# Teensy-Maxuino-Slave-A4988-stepper_2x_sh.net
KiCad netlist of a schematic drawn in EAGLE
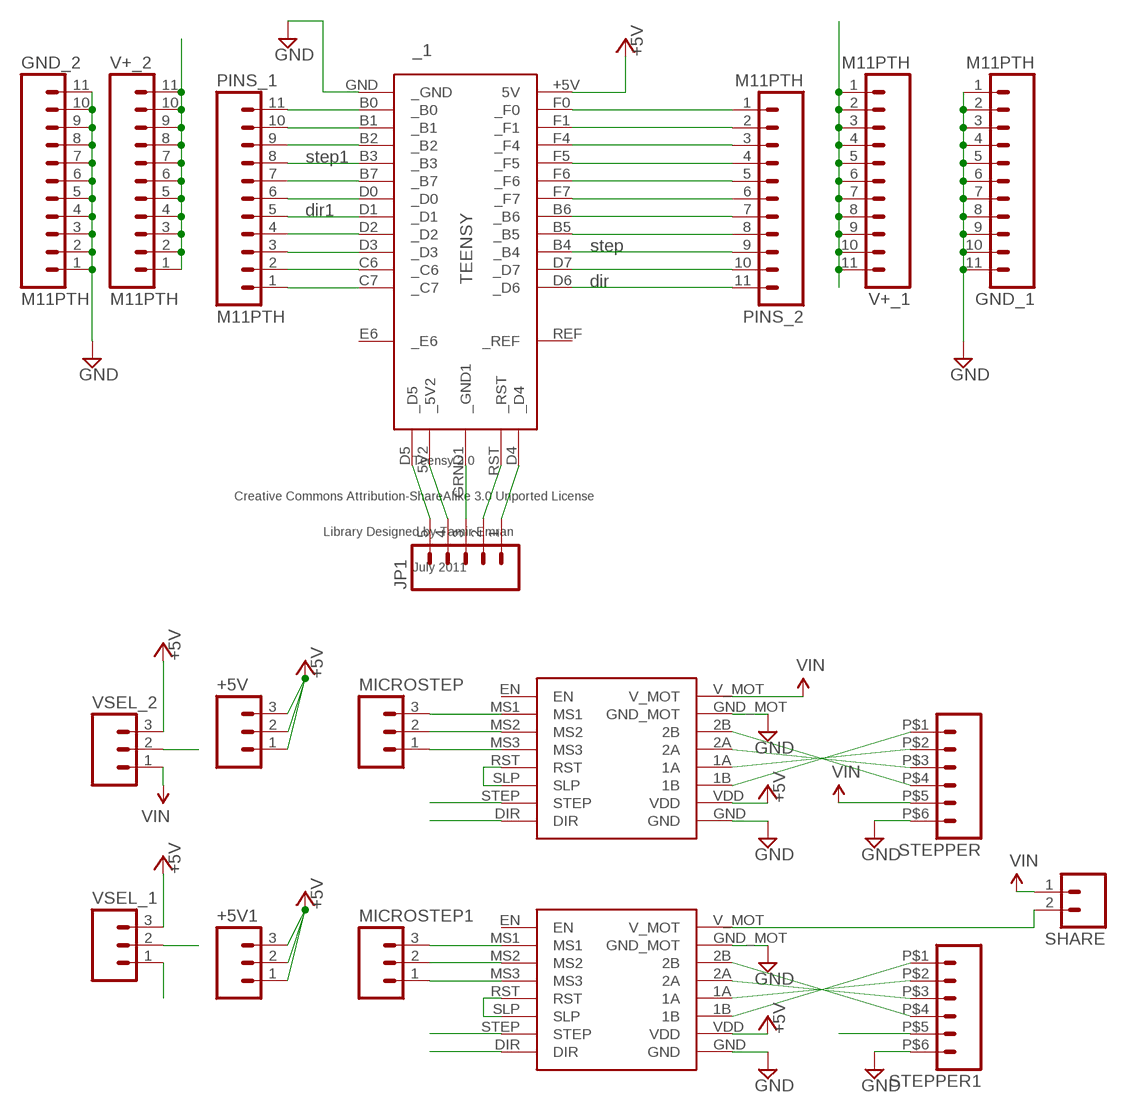
[diagram p0: schematic, sheet 1]

(export (version "E")
  (design (tool "Eeschema 10.0.6"))
  (components
    (comp (ref "+5V")
      (value "M03PTH")
      (footprint "eagle-import:1X03")
      (libsource (lib "eagle-import") (part "M03PTH"))
    )
    (comp (ref "+5V1")
      (value "M03PTH")
      (footprint "eagle-import:1X03")
      (libsource (lib "eagle-import") (part "M03PTH"))
    )
    (comp (ref "A4988_1")
      (value "POLOLU_A4988")
      (footprint "eagle-import:POLOLU_A4988")
      (libsource (lib "eagle-import") (part "POLOLU_A4988"))
    )
    (comp (ref "A4988_2")
      (value "POLOLU_A4988")
      (footprint "eagle-import:POLOLU_A4988")
      (libsource (lib "eagle-import") (part "POLOLU_A4988"))
    )
    (comp (ref "GND_1")
      (value "M11PTH")
      (footprint "eagle-import:1X11")
      (libsource (lib "eagle-import") (part "M11PTH"))
    )
    (comp (ref "GND_2")
      (value "M11PTH")
      (footprint "eagle-import:1X11")
      (libsource (lib "eagle-import") (part "M11PTH"))
    )
    (comp (ref "JP1")
      (value "M05PTH")
      (footprint "eagle-import:1X05")
      (libsource (lib "eagle-import") (part "M05PTH"))
    )
    (comp (ref "MICROSTEP")
      (value "M03PTH")
      (footprint "eagle-import:1X03")
      (libsource (lib "eagle-import") (part "M03PTH"))
    )
    (comp (ref "MICROSTEP1")
      (value "M03PTH")
      (footprint "eagle-import:1X03")
      (libsource (lib "eagle-import") (part "M03PTH"))
    )
    (comp (ref "PINS_1")
      (value "M11PTH")
      (footprint "eagle-import:1X11")
      (libsource (lib "eagle-import") (part "M11PTH"))
    )
    (comp (ref "PINS_2")
      (value "M11PTH")
      (footprint "eagle-import:1X11")
      (libsource (lib "eagle-import") (part "M11PTH"))
    )
    (comp (ref "SHARE")
      (value "M02PTH")
      (footprint "eagle-import:1X02")
      (libsource (lib "eagle-import") (part "M02PTH"))
    )
    (comp (ref "STEPPER")
      (value "M06")
      (footprint "eagle-import:SPRINGTERMINAL-2.54MM-6")
      (libsource (lib "eagle-import") (part "M06"))
    )
    (comp (ref "STEPPER1")
      (value "M06")
      (footprint "eagle-import:SPRINGTERMINAL-2.54MM-6")
      (libsource (lib "eagle-import") (part "M06"))
    )
    (comp (ref "V+_1")
      (value "M11PTH")
      (footprint "eagle-import:1X11")
      (libsource (lib "eagle-import") (part "M11PTH"))
    )
    (comp (ref "V+_2")
      (value "M11PTH")
      (footprint "eagle-import:1X11")
      (libsource (lib "eagle-import") (part "M11PTH"))
    )
    (comp (ref "VSEL_1")
      (value "M03PTH")
      (footprint "eagle-import:1X03")
      (libsource (lib "eagle-import") (part "M03PTH"))
    )
    (comp (ref "VSEL_2")
      (value "M03PTH")
      (footprint "eagle-import:1X03")
      (libsource (lib "eagle-import") (part "M03PTH"))
    )
    (comp (ref "_1")
      (value "TEENSY")
      (footprint "eagle-import:TEENSY")
      (libsource (lib "eagle-import") (part "TEENSY"))
    )
  )
  (nets
    (net (code "1") (name "+5V") (class "Default")
      (node (ref "+5V") (pin "1") (pinfunction "1_1") (pintype "passive"))
      (node (ref "+5V") (pin "2") (pinfunction "2_2") (pintype "passive"))
      (node (ref "+5V") (pin "3") (pinfunction "3_3") (pintype "passive"))
      (node (ref "+5V1") (pin "1") (pinfunction "1_1") (pintype "passive"))
      (node (ref "+5V1") (pin "2") (pinfunction "2_2") (pintype "passive"))
      (node (ref "+5V1") (pin "3") (pinfunction "3_3") (pintype "passive"))
      (node (ref "A4988_1") (pin "VDD") (pinfunction "VDD_VDD") (pintype "bidirectional"))
      (node (ref "A4988_2") (pin "VDD") (pinfunction "VDD_VDD") (pintype "bidirectional"))
      (node (ref "JP1") (pin "4") (pinfunction "4_4") (pintype "passive"))
      (node (ref "VSEL_1") (pin "3") (pinfunction "3_3") (pintype "passive"))
      (node (ref "VSEL_2") (pin "3") (pinfunction "3_3") (pintype "passive"))
      (node (ref "_1") (pin "+5V") (pinfunction "5V_+5V") (pintype "bidirectional"))
      (node (ref "_1") (pin "5V2") (pinfunction "_5V2_5V2") (pintype "bidirectional"))
    )
    (net (code "2") (name "/DIR") (class "Default")
      (node (ref "A4988_1") (pin "DIR") (pinfunction "DIR_DIR") (pintype "bidirectional"))
      (node (ref "PINS_2") (pin "11") (pinfunction "11_11") (pintype "passive"))
      (node (ref "_1") (pin "D6") (pinfunction "_D6_D6") (pintype "bidirectional"))
    )
    (net (code "3") (name "/DIR1") (class "Default")
      (node (ref "A4988_2") (pin "DIR") (pinfunction "DIR_DIR") (pintype "bidirectional"))
      (node (ref "PINS_1") (pin "5") (pinfunction "5_5") (pintype "passive"))
      (node (ref "_1") (pin "D1") (pinfunction "_D1_D1") (pintype "bidirectional"))
    )
    (net (code "4") (name "/STEP") (class "Default")
      (node (ref "A4988_1") (pin "STEP") (pinfunction "STEP_STEP") (pintype "bidirectional"))
      (node (ref "PINS_2") (pin "9") (pinfunction "9_9") (pintype "passive"))
      (node (ref "_1") (pin "B4") (pinfunction "_B4_B4") (pintype "bidirectional"))
    )
    (net (code "5") (name "/STEP1") (class "Default")
      (node (ref "A4988_2") (pin "STEP") (pinfunction "STEP_STEP") (pintype "bidirectional"))
      (node (ref "PINS_1") (pin "8") (pinfunction "8_8") (pintype "passive"))
      (node (ref "_1") (pin "B3") (pinfunction "_B3_B3") (pintype "bidirectional"))
    )
    (net (code "6") (name "/V+_1") (class "Default")
      (node (ref "V+_1") (pin "1") (pinfunction "1_1") (pintype "passive"))
      (node (ref "V+_1") (pin "10") (pinfunction "10_10") (pintype "passive"))
      (node (ref "V+_1") (pin "11") (pinfunction "11_11") (pintype "passive"))
      (node (ref "V+_1") (pin "2") (pinfunction "2_2") (pintype "passive"))
      (node (ref "V+_1") (pin "3") (pinfunction "3_3") (pintype "passive"))
      (node (ref "V+_1") (pin "4") (pinfunction "4_4") (pintype "passive"))
      (node (ref "V+_1") (pin "5") (pinfunction "5_5") (pintype "passive"))
      (node (ref "V+_1") (pin "6") (pinfunction "6_6") (pintype "passive"))
      (node (ref "V+_1") (pin "7") (pinfunction "7_7") (pintype "passive"))
      (node (ref "V+_1") (pin "8") (pinfunction "8_8") (pintype "passive"))
      (node (ref "V+_1") (pin "9") (pinfunction "9_9") (pintype "passive"))
      (node (ref "VSEL_1") (pin "2") (pinfunction "2_2") (pintype "passive"))
    )
    (net (code "7") (name "/V+_2") (class "Default")
      (node (ref "V+_2") (pin "1") (pinfunction "1_1") (pintype "passive"))
      (node (ref "V+_2") (pin "10") (pinfunction "10_10") (pintype "passive"))
      (node (ref "V+_2") (pin "11") (pinfunction "11_11") (pintype "passive"))
      (node (ref "V+_2") (pin "2") (pinfunction "2_2") (pintype "passive"))
      (node (ref "V+_2") (pin "3") (pinfunction "3_3") (pintype "passive"))
      (node (ref "V+_2") (pin "4") (pinfunction "4_4") (pintype "passive"))
      (node (ref "V+_2") (pin "5") (pinfunction "5_5") (pintype "passive"))
      (node (ref "V+_2") (pin "6") (pinfunction "6_6") (pintype "passive"))
      (node (ref "V+_2") (pin "7") (pinfunction "7_7") (pintype "passive"))
      (node (ref "V+_2") (pin "8") (pinfunction "8_8") (pintype "passive"))
      (node (ref "V+_2") (pin "9") (pinfunction "9_9") (pintype "passive"))
      (node (ref "VSEL_2") (pin "2") (pinfunction "2_2") (pintype "passive"))
    )
    (net (code "8") (name "/VIN_2") (class "Default")
      (node (ref "A4988_2") (pin "V_MOT") (pinfunction "V_MOT_V_MOT") (pintype "bidirectional"))
      (node (ref "SHARE") (pin "2") (pinfunction "2_2") (pintype "passive"))
      (node (ref "STEPPER1") (pin "P$5") (pinfunction "5_P$5") (pintype "passive"))
      (node (ref "VSEL_1") (pin "1") (pinfunction "1_1") (pintype "passive"))
    )
    (net (code "9") (name "GND") (class "Default")
      (node (ref "A4988_1") (pin "GND") (pinfunction "GND_GND") (pintype "bidirectional"))
      (node (ref "A4988_1") (pin "GND_MOT") (pinfunction "GND_MOT_GND_MOT") (pintype "bidirectional"))
      (node (ref "A4988_2") (pin "GND") (pinfunction "GND_GND") (pintype "bidirectional"))
      (node (ref "A4988_2") (pin "GND_MOT") (pinfunction "GND_MOT_GND_MOT") (pintype "bidirectional"))
      (node (ref "GND_1") (pin "1") (pinfunction "1_1") (pintype "passive"))
      (node (ref "GND_1") (pin "10") (pinfunction "10_10") (pintype "passive"))
      (node (ref "GND_1") (pin "11") (pinfunction "11_11") (pintype "passive"))
      (node (ref "GND_1") (pin "2") (pinfunction "2_2") (pintype "passive"))
      (node (ref "GND_1") (pin "3") (pinfunction "3_3") (pintype "passive"))
      (node (ref "GND_1") (pin "4") (pinfunction "4_4") (pintype "passive"))
      (node (ref "GND_1") (pin "5") (pinfunction "5_5") (pintype "passive"))
      (node (ref "GND_1") (pin "6") (pinfunction "6_6") (pintype "passive"))
      (node (ref "GND_1") (pin "7") (pinfunction "7_7") (pintype "passive"))
      (node (ref "GND_1") (pin "8") (pinfunction "8_8") (pintype "passive"))
      (node (ref "GND_1") (pin "9") (pinfunction "9_9") (pintype "passive"))
      (node (ref "GND_2") (pin "1") (pinfunction "1_1") (pintype "passive"))
      (node (ref "GND_2") (pin "10") (pinfunction "10_10") (pintype "passive"))
      (node (ref "GND_2") (pin "11") (pinfunction "11_11") (pintype "passive"))
      (node (ref "GND_2") (pin "2") (pinfunction "2_2") (pintype "passive"))
      (node (ref "GND_2") (pin "3") (pinfunction "3_3") (pintype "passive"))
      (node (ref "GND_2") (pin "4") (pinfunction "4_4") (pintype "passive"))
      (node (ref "GND_2") (pin "5") (pinfunction "5_5") (pintype "passive"))
      (node (ref "GND_2") (pin "6") (pinfunction "6_6") (pintype "passive"))
      (node (ref "GND_2") (pin "7") (pinfunction "7_7") (pintype "passive"))
      (node (ref "GND_2") (pin "8") (pinfunction "8_8") (pintype "passive"))
      (node (ref "GND_2") (pin "9") (pinfunction "9_9") (pintype "passive"))
      (node (ref "JP1") (pin "3") (pinfunction "3_3") (pintype "passive"))
      (node (ref "STEPPER") (pin "P$6") (pinfunction "6_P$6") (pintype "passive"))
      (node (ref "STEPPER1") (pin "P$6") (pinfunction "6_P$6") (pintype "passive"))
      (node (ref "_1") (pin "GND") (pinfunction "_GND_GND") (pintype "bidirectional"))
      (node (ref "_1") (pin "GRND1") (pinfunction "_GND1_GRND1") (pintype "bidirectional"))
    )
    (net (code "10") (name "Net-(A4988_1-PadMS1)") (class "Default")
      (node (ref "A4988_1") (pin "MS1") (pinfunction "MS1_MS1") (pintype "bidirectional"))
      (node (ref "MICROSTEP") (pin "3") (pinfunction "3_3") (pintype "passive"))
    )
    (net (code "11") (name "Net-(A4988_1-PadMS2)") (class "Default")
      (node (ref "A4988_1") (pin "MS2") (pinfunction "MS2_MS2") (pintype "bidirectional"))
      (node (ref "MICROSTEP") (pin "2") (pinfunction "2_2") (pintype "passive"))
    )
    (net (code "12") (name "Net-(A4988_1-PadMS3)") (class "Default")
      (node (ref "A4988_1") (pin "MS3") (pinfunction "MS3_MS3") (pintype "bidirectional"))
      (node (ref "MICROSTEP") (pin "1") (pinfunction "1_1") (pintype "passive"))
    )
    (net (code "13") (name "Net-(A4988_1-PadRST)") (class "Default")
      (node (ref "A4988_1") (pin "RST") (pinfunction "RST_RST") (pintype "bidirectional"))
      (node (ref "A4988_1") (pin "SLP") (pinfunction "SLP_SLP") (pintype "bidirectional"))
    )
    (net (code "14") (name "Net-(A4988_2-PadMS1)") (class "Default")
      (node (ref "A4988_2") (pin "MS1") (pinfunction "MS1_MS1") (pintype "bidirectional"))
      (node (ref "MICROSTEP1") (pin "3") (pinfunction "3_3") (pintype "passive"))
    )
    (net (code "15") (name "Net-(A4988_2-PadMS2)") (class "Default")
      (node (ref "A4988_2") (pin "MS2") (pinfunction "MS2_MS2") (pintype "bidirectional"))
      (node (ref "MICROSTEP1") (pin "2") (pinfunction "2_2") (pintype "passive"))
    )
    (net (code "16") (name "Net-(A4988_2-PadMS3)") (class "Default")
      (node (ref "A4988_2") (pin "MS3") (pinfunction "MS3_MS3") (pintype "bidirectional"))
      (node (ref "MICROSTEP1") (pin "1") (pinfunction "1_1") (pintype "passive"))
    )
    (net (code "17") (name "Net-(A4988_2-PadRST)") (class "Default")
      (node (ref "A4988_2") (pin "RST") (pinfunction "RST_RST") (pintype "bidirectional"))
      (node (ref "A4988_2") (pin "SLP") (pinfunction "SLP_SLP") (pintype "bidirectional"))
    )
    (net (code "18") (name "Net-(STEPPER-1)") (class "Default")
      (node (ref "A4988_1") (pin "1B") (pinfunction "1B_1B") (pintype "bidirectional"))
      (node (ref "STEPPER") (pin "P$1") (pinfunction "1_P$1") (pintype "passive"))
    )
    (net (code "19") (name "Net-(STEPPER-2)") (class "Default")
      (node (ref "A4988_1") (pin "1A") (pinfunction "1A_1A") (pintype "bidirectional"))
      (node (ref "STEPPER") (pin "P$2") (pinfunction "2_P$2") (pintype "passive"))
    )
    (net (code "20") (name "Net-(STEPPER-3)") (class "Default")
      (node (ref "A4988_1") (pin "2A") (pinfunction "2A_2A") (pintype "bidirectional"))
      (node (ref "STEPPER") (pin "P$3") (pinfunction "3_P$3") (pintype "passive"))
    )
    (net (code "21") (name "Net-(STEPPER-4)") (class "Default")
      (node (ref "A4988_1") (pin "2B") (pinfunction "2B_2B") (pintype "bidirectional"))
      (node (ref "STEPPER") (pin "P$4") (pinfunction "4_P$4") (pintype "passive"))
    )
    (net (code "22") (name "Net-(STEPPER1-1)") (class "Default")
      (node (ref "A4988_2") (pin "1B") (pinfunction "1B_1B") (pintype "bidirectional"))
      (node (ref "STEPPER1") (pin "P$1") (pinfunction "1_P$1") (pintype "passive"))
    )
    (net (code "23") (name "Net-(STEPPER1-2)") (class "Default")
      (node (ref "A4988_2") (pin "1A") (pinfunction "1A_1A") (pintype "bidirectional"))
      (node (ref "STEPPER1") (pin "P$2") (pinfunction "2_P$2") (pintype "passive"))
    )
    (net (code "24") (name "Net-(STEPPER1-3)") (class "Default")
      (node (ref "A4988_2") (pin "2A") (pinfunction "2A_2A") (pintype "bidirectional"))
      (node (ref "STEPPER1") (pin "P$3") (pinfunction "3_P$3") (pintype "passive"))
    )
    (net (code "25") (name "Net-(STEPPER1-4)") (class "Default")
      (node (ref "A4988_2") (pin "2B") (pinfunction "2B_2B") (pintype "bidirectional"))
      (node (ref "STEPPER1") (pin "P$4") (pinfunction "4_P$4") (pintype "passive"))
    )
    (net (code "26") (name "Net-(_1-_B0)") (class "Default")
      (node (ref "PINS_1") (pin "11") (pinfunction "11_11") (pintype "passive"))
      (node (ref "_1") (pin "B0") (pinfunction "_B0_B0") (pintype "bidirectional"))
    )
    (net (code "27") (name "Net-(_1-_B1)") (class "Default")
      (node (ref "PINS_1") (pin "10") (pinfunction "10_10") (pintype "passive"))
      (node (ref "_1") (pin "B1") (pinfunction "_B1_B1") (pintype "bidirectional"))
    )
    (net (code "28") (name "Net-(_1-_B2)") (class "Default")
      (node (ref "PINS_1") (pin "9") (pinfunction "9_9") (pintype "passive"))
      (node (ref "_1") (pin "B2") (pinfunction "_B2_B2") (pintype "bidirectional"))
    )
    (net (code "29") (name "Net-(_1-_B5)") (class "Default")
      (node (ref "PINS_2") (pin "8") (pinfunction "8_8") (pintype "passive"))
      (node (ref "_1") (pin "B5") (pinfunction "_B5_B5") (pintype "bidirectional"))
    )
    (net (code "30") (name "Net-(_1-_B6)") (class "Default")
      (node (ref "PINS_2") (pin "7") (pinfunction "7_7") (pintype "passive"))
      (node (ref "_1") (pin "B6") (pinfunction "_B6_B6") (pintype "bidirectional"))
    )
    (net (code "31") (name "Net-(_1-_B7)") (class "Default")
      (node (ref "PINS_1") (pin "7") (pinfunction "7_7") (pintype "passive"))
      (node (ref "_1") (pin "B7") (pinfunction "_B7_B7") (pintype "bidirectional"))
    )
    (net (code "32") (name "Net-(_1-_C6)") (class "Default")
      (node (ref "PINS_1") (pin "2") (pinfunction "2_2") (pintype "passive"))
      (node (ref "_1") (pin "C6") (pinfunction "_C6_C6") (pintype "bidirectional"))
    )
    (net (code "33") (name "Net-(_1-_C7)") (class "Default")
      (node (ref "PINS_1") (pin "1") (pinfunction "1_1") (pintype "passive"))
      (node (ref "_1") (pin "C7") (pinfunction "_C7_C7") (pintype "bidirectional"))
    )
    (net (code "34") (name "Net-(_1-_D0)") (class "Default")
      (node (ref "PINS_1") (pin "6") (pinfunction "6_6") (pintype "passive"))
      (node (ref "_1") (pin "D0") (pinfunction "_D0_D0") (pintype "bidirectional"))
    )
    (net (code "35") (name "Net-(_1-_D2)") (class "Default")
      (node (ref "PINS_1") (pin "4") (pinfunction "4_4") (pintype "passive"))
      (node (ref "_1") (pin "D2") (pinfunction "_D2_D2") (pintype "bidirectional"))
    )
    (net (code "36") (name "Net-(_1-_D3)") (class "Default")
      (node (ref "PINS_1") (pin "3") (pinfunction "3_3") (pintype "passive"))
      (node (ref "_1") (pin "D3") (pinfunction "_D3_D3") (pintype "bidirectional"))
    )
    (net (code "37") (name "Net-(_1-_D4)") (class "Default")
      (node (ref "JP1") (pin "1") (pinfunction "1_1") (pintype "passive"))
      (node (ref "_1") (pin "D4") (pinfunction "_D4_D4") (pintype "bidirectional"))
    )
    (net (code "38") (name "Net-(_1-_D5)") (class "Default")
      (node (ref "JP1") (pin "5") (pinfunction "5_5") (pintype "passive"))
      (node (ref "_1") (pin "D5") (pinfunction "_D5_D5") (pintype "bidirectional"))
    )
    (net (code "39") (name "Net-(_1-_D7)") (class "Default")
      (node (ref "PINS_2") (pin "10") (pinfunction "10_10") (pintype "passive"))
      (node (ref "_1") (pin "D7") (pinfunction "_D7_D7") (pintype "bidirectional"))
    )
    (net (code "40") (name "Net-(_1-_F0)") (class "Default")
      (node (ref "PINS_2") (pin "1") (pinfunction "1_1") (pintype "passive"))
      (node (ref "_1") (pin "F0") (pinfunction "_F0_F0") (pintype "bidirectional"))
    )
    (net (code "41") (name "Net-(_1-_F1)") (class "Default")
      (node (ref "PINS_2") (pin "2") (pinfunction "2_2") (pintype "passive"))
      (node (ref "_1") (pin "F1") (pinfunction "_F1_F1") (pintype "bidirectional"))
    )
    (net (code "42") (name "Net-(_1-_F4)") (class "Default")
      (node (ref "PINS_2") (pin "3") (pinfunction "3_3") (pintype "passive"))
      (node (ref "_1") (pin "F4") (pinfunction "_F4_F4") (pintype "bidirectional"))
    )
    (net (code "43") (name "Net-(_1-_F5)") (class "Default")
      (node (ref "PINS_2") (pin "4") (pinfunction "4_4") (pintype "passive"))
      (node (ref "_1") (pin "F5") (pinfunction "_F5_F5") (pintype "bidirectional"))
    )
    (net (code "44") (name "Net-(_1-_F6)") (class "Default")
      (node (ref "PINS_2") (pin "5") (pinfunction "5_5") (pintype "passive"))
      (node (ref "_1") (pin "F6") (pinfunction "_F6_F6") (pintype "bidirectional"))
    )
    (net (code "45") (name "Net-(_1-_F7)") (class "Default")
      (node (ref "PINS_2") (pin "6") (pinfunction "6_6") (pintype "passive"))
      (node (ref "_1") (pin "F7") (pinfunction "_F7_F7") (pintype "bidirectional"))
    )
    (net (code "46") (name "Net-(_1-_RST)") (class "Default")
      (node (ref "JP1") (pin "2") (pinfunction "2_2") (pintype "passive"))
      (node (ref "_1") (pin "RST") (pinfunction "_RST_RST") (pintype "bidirectional"))
    )
    (net (code "47") (name "VIN") (class "Default")
      (node (ref "A4988_1") (pin "V_MOT") (pinfunction "V_MOT_V_MOT") (pintype "bidirectional"))
      (node (ref "SHARE") (pin "1") (pinfunction "1_1") (pintype "passive"))
      (node (ref "STEPPER") (pin "P$5") (pinfunction "5_P$5") (pintype "passive"))
      (node (ref "VSEL_2") (pin "1") (pinfunction "1_1") (pintype "passive"))
    )
    (net (code "48") (name "unconnected-(A4988_1-PadEN)") (class "Default")
      (node (ref "A4988_1") (pin "EN") (pinfunction "EN_EN") (pintype "bidirectional"))
    )
    (net (code "49") (name "unconnected-(A4988_2-PadEN)") (class "Default")
      (node (ref "A4988_2") (pin "EN") (pinfunction "EN_EN") (pintype "bidirectional"))
    )
    (net (code "50") (name "unconnected-(_1-_E6-PadE6)") (class "Default")
      (node (ref "_1") (pin "E6") (pinfunction "_E6_E6") (pintype "bidirectional"))
    )
    (net (code "51") (name "unconnected-(_1-_REF-PadREF)") (class "Default")
      (node (ref "_1") (pin "REF") (pinfunction "_REF_REF") (pintype "bidirectional"))
    )
  )
)
